# TubeBoard-Logic.net
KiCad netlist of a schematic drawn in EAGLE
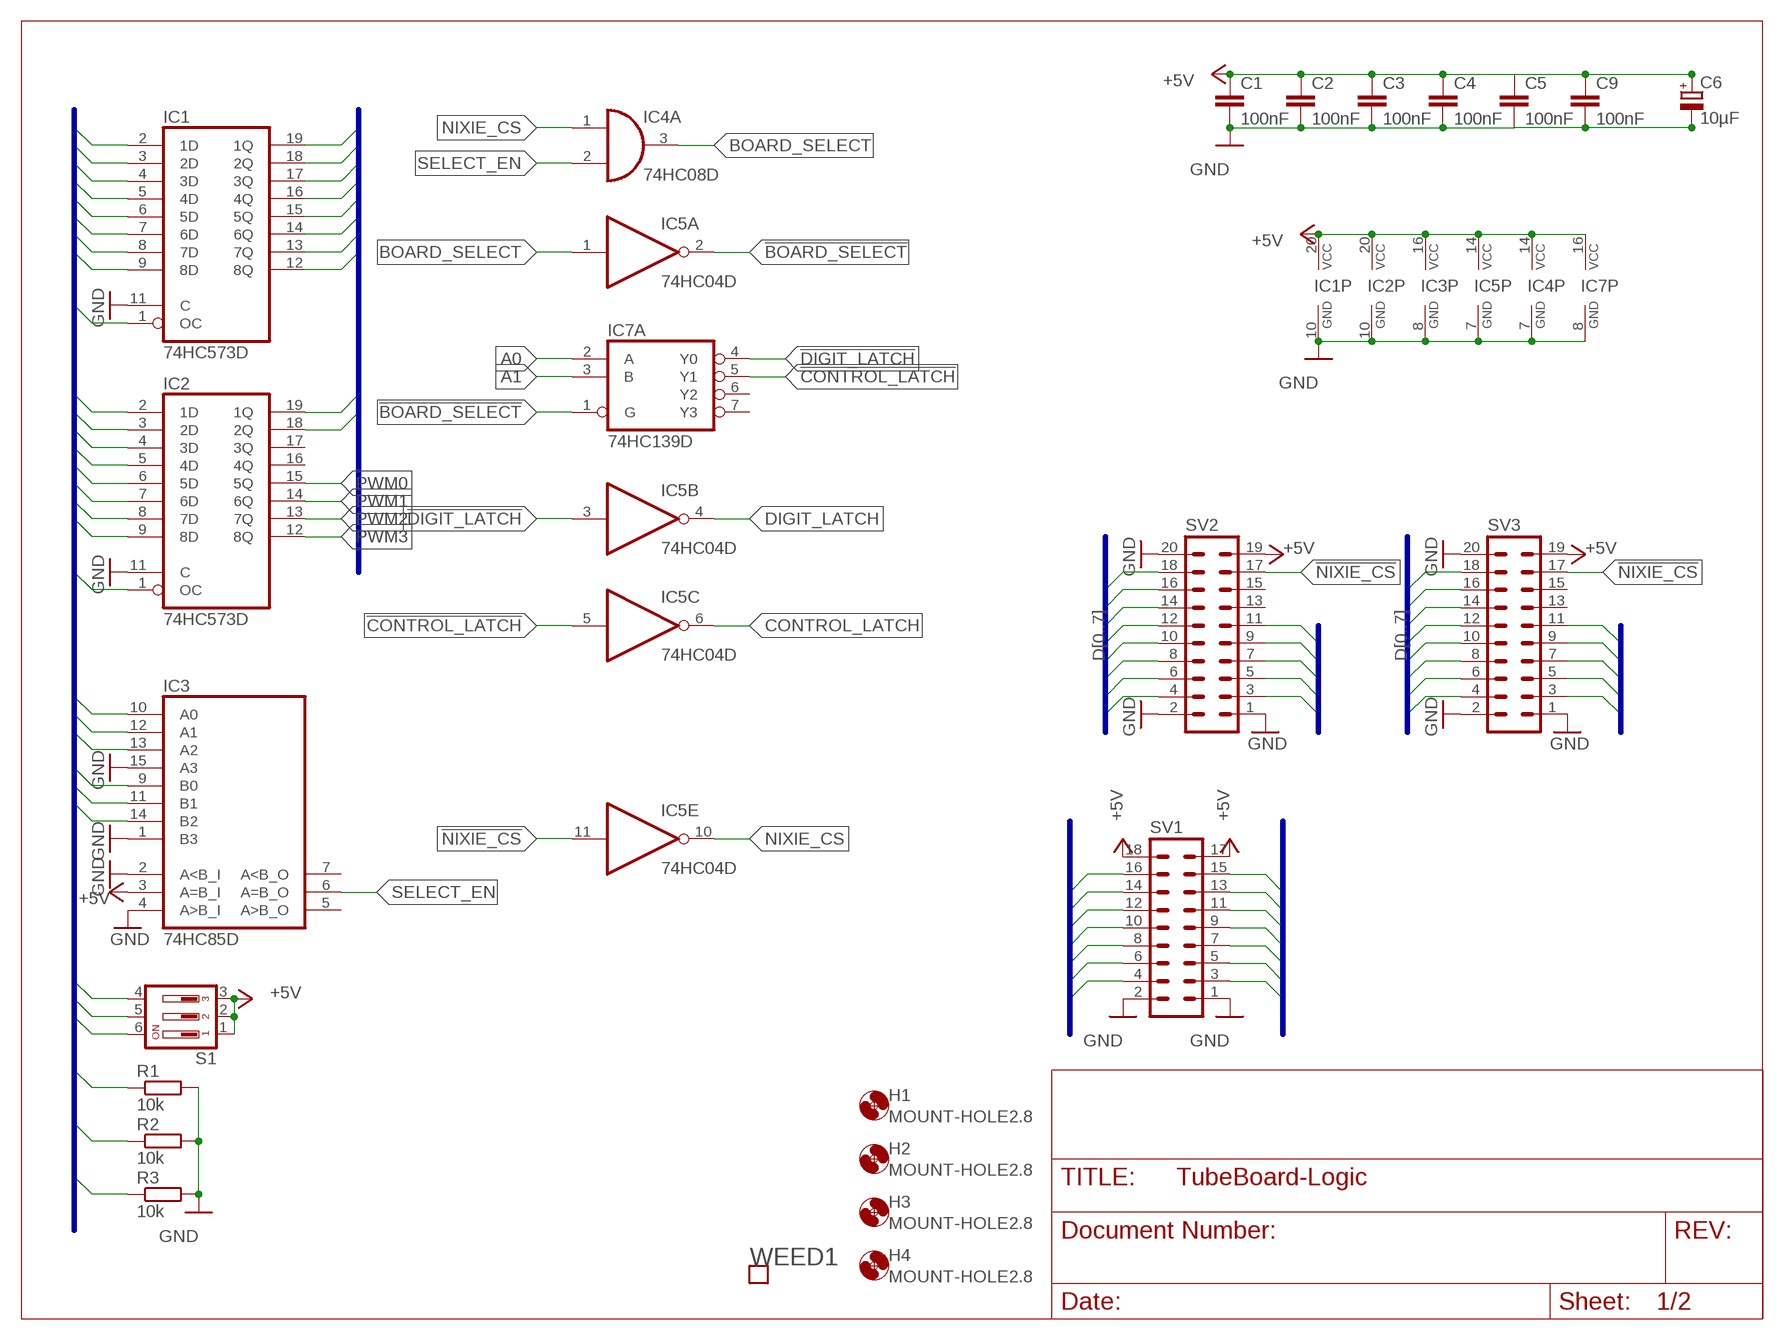
[diagram p0: schematic, sheet 1]
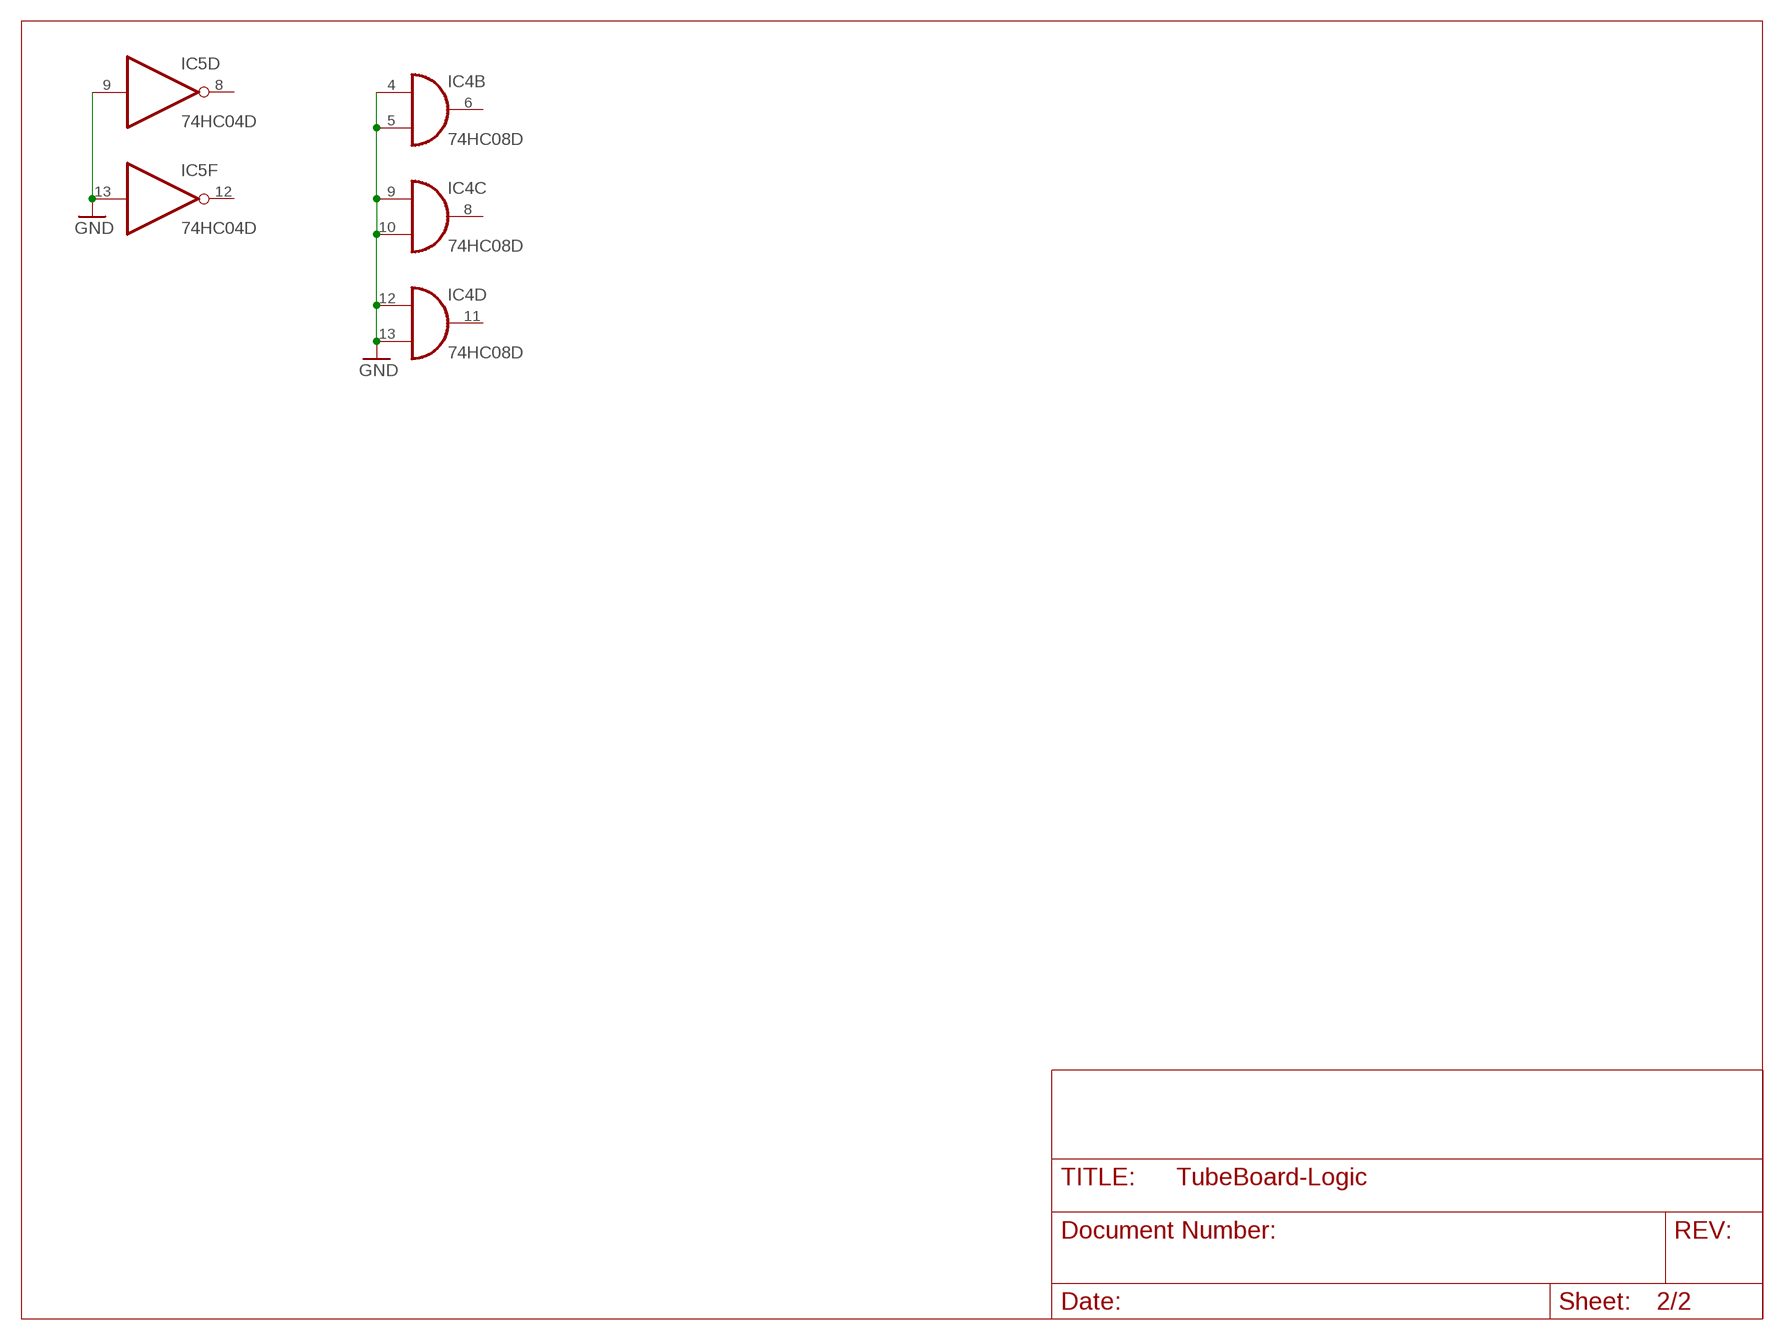
[diagram p1: schematic, sheet 2]

(export (version "E")
  (design (tool "Eeschema 10.0.6"))
  (components
    (comp (ref "C1")
      (value "100nF")
      (footprint "eagle-import:C1206")
      (libsource (lib "eagle-import") (part "C-EUC1206"))
    )
    (comp (ref "C2")
      (value "100nF")
      (footprint "eagle-import:C1206")
      (libsource (lib "eagle-import") (part "C-EUC1206"))
    )
    (comp (ref "C3")
      (value "100nF")
      (footprint "eagle-import:C1206")
      (libsource (lib "eagle-import") (part "C-EUC1206"))
    )
    (comp (ref "C4")
      (value "100nF")
      (footprint "eagle-import:C1206")
      (libsource (lib "eagle-import") (part "C-EUC1206"))
    )
    (comp (ref "C5")
      (value "100nF")
      (footprint "eagle-import:C1206")
      (libsource (lib "eagle-import") (part "C-EUC1206"))
    )
    (comp (ref "C6")
      (value "10µF")
      (footprint "eagle-import:SMC_B")
      (libsource (lib "eagle-import") (part "CPOL-EUSMCB"))
    )
    (comp (ref "C9")
      (value "100nF")
      (footprint "eagle-import:C1206")
      (libsource (lib "eagle-import") (part "C-EUC1206"))
    )
    (comp (ref "H1")
      (value "MOUNT-HOLE2.8")
      (footprint "eagle-import:2,8")
      (libsource (lib "eagle-import") (part "MOUNT-HOLE2.8"))
    )
    (comp (ref "H2")
      (value "MOUNT-HOLE2.8")
      (footprint "eagle-import:2,8")
      (libsource (lib "eagle-import") (part "MOUNT-HOLE2.8"))
    )
    (comp (ref "H3")
      (value "MOUNT-HOLE2.8")
      (footprint "eagle-import:2,8")
      (libsource (lib "eagle-import") (part "MOUNT-HOLE2.8"))
    )
    (comp (ref "H4")
      (value "MOUNT-HOLE2.8")
      (footprint "eagle-import:2,8")
      (libsource (lib "eagle-import") (part "MOUNT-HOLE2.8"))
    )
    (comp (ref "IC1")
      (value "74HC573D")
      (footprint "eagle-import:SO20W")
      (libsource (lib "eagle-import") (part "74573DHC"))
    )
    (comp (ref "IC2")
      (value "74HC573D")
      (footprint "eagle-import:SO20W")
      (libsource (lib "eagle-import") (part "74573DHC"))
    )
    (comp (ref "IC3")
      (value "74HC85D")
      (footprint "eagle-import:SO16")
      (fields (field (name "MOUSER") "771-74HC85D-T"))
      (libsource (lib "eagle-import") (part "7485DHC"))
    )
    (comp (ref "IC4")
      (value "74HC08D")
      (footprint "eagle-import:SO14")
      (libsource (lib "eagle-import") (part "7408DHC"))
    )
    (comp (ref "IC5")
      (value "74HC04D")
      (footprint "eagle-import:SO14")
      (libsource (lib "eagle-import") (part "7404DHC"))
    )
    (comp (ref "IC7")
      (value "74HC139D")
      (footprint "eagle-import:SO16")
      (fields (field (name "MOUSER") "771-HC139D652"))
      (libsource (lib "eagle-import") (part "74139DHC"))
    )
    (comp (ref "R1")
      (value "10k")
      (footprint "eagle-import:R2012")
      (libsource (lib "eagle-import") (part "R-EU_R2012"))
    )
    (comp (ref "R2")
      (value "10k")
      (footprint "eagle-import:R2012")
      (libsource (lib "eagle-import") (part "R-EU_R2012"))
    )
    (comp (ref "R3")
      (value "10k")
      (footprint "eagle-import:R2012")
      (libsource (lib "eagle-import") (part "R-EU_R2012"))
    )
    (comp (ref "S1")
      (value "SD4-03")
      (footprint "eagle-import:SD4-03")
      (libsource (lib "eagle-import") (part "SD4-03"))
    )
    (comp (ref "SV1")
      (value "MA09-2")
      (footprint "eagle-import:MA09-2")
      (libsource (lib "eagle-import") (part "MA09-2"))
    )
    (comp (ref "SV2")
      (value "MA10-2")
      (footprint "eagle-import:MA10-2")
      (libsource (lib "eagle-import") (part "MA10-2"))
    )
    (comp (ref "SV3")
      (value "MA10-2")
      (footprint "eagle-import:MA10-2")
      (libsource (lib "eagle-import") (part "MA10-2"))
    )
    (comp (ref "WEED1")
      (value "WEED")
      (footprint "eagle-import:DOINK")
      (libsource (lib "eagle-import") (part "WEED"))
    )
  )
  (nets
    (net (code "16") (name "+5V") (class "Default")
      (node (ref "C1") (pin "1") (pinfunction "1_1") (pintype "passive"))
      (node (ref "C2") (pin "1") (pinfunction "1_1") (pintype "passive"))
      (node (ref "C3") (pin "1") (pinfunction "1_1") (pintype "passive"))
      (node (ref "C4") (pin "1") (pinfunction "1_1") (pintype "passive"))
      (node (ref "C5") (pin "1") (pinfunction "1_1") (pintype "passive"))
      (node (ref "C6") (pin "+") (pinfunction "+_+") (pintype "passive"))
      (node (ref "C9") (pin "1") (pinfunction "1_1") (pintype "passive"))
      (node (ref "IC1") (pin "20") (pinfunction "VCC_20") (pintype "power_in"))
      (node (ref "IC2") (pin "20") (pinfunction "VCC_20") (pintype "power_in"))
      (node (ref "IC3") (pin "16") (pinfunction "VCC_16") (pintype "power_in"))
      (node (ref "IC3") (pin "3") (pinfunction "A=B_I_3") (pintype "input"))
      (node (ref "IC4") (pin "14") (pinfunction "VCC_14") (pintype "power_in"))
      (node (ref "IC5") (pin "14") (pinfunction "VCC_14") (pintype "power_in"))
      (node (ref "IC7") (pin "16") (pinfunction "VCC_16") (pintype "power_in"))
      (node (ref "S1") (pin "1") (pinfunction "1_1") (pintype "passive"))
      (node (ref "S1") (pin "2") (pinfunction "2_2") (pintype "passive"))
      (node (ref "S1") (pin "3") (pinfunction "3_3") (pintype "passive"))
      (node (ref "SV1") (pin "17") (pinfunction "17_17") (pintype "passive"))
      (node (ref "SV1") (pin "18") (pinfunction "18_18") (pintype "passive"))
      (node (ref "SV2") (pin "19") (pinfunction "19_19") (pintype "passive"))
      (node (ref "SV3") (pin "19") (pinfunction "19_19") (pintype "passive"))
    )
    (net (code "20") (name "A0") (class "Default")
      (node (ref "IC7") (pin "2") (pinfunction "A_2") (pintype "input"))
      (node (ref "SV2") (pin "3") (pinfunction "3_3") (pintype "passive"))
      (node (ref "SV3") (pin "3") (pinfunction "3_3") (pintype "passive"))
    )
    (net (code "21") (name "A1") (class "Default")
      (node (ref "IC7") (pin "3") (pinfunction "B_3") (pintype "input"))
      (node (ref "SV2") (pin "5") (pinfunction "5_5") (pintype "passive"))
      (node (ref "SV3") (pin "5") (pinfunction "5_5") (pintype "passive"))
    )
    (net (code "22") (name "A2") (class "Default")
      (node (ref "IC3") (pin "10") (pinfunction "A0_10") (pintype "input"))
      (node (ref "SV2") (pin "7") (pinfunction "7_7") (pintype "passive"))
      (node (ref "SV3") (pin "7") (pinfunction "7_7") (pintype "passive"))
    )
    (net (code "23") (name "A3") (class "Default")
      (node (ref "IC3") (pin "12") (pinfunction "A1_12") (pintype "input"))
      (node (ref "SV2") (pin "9") (pinfunction "9_9") (pintype "passive"))
      (node (ref "SV3") (pin "9") (pinfunction "9_9") (pintype "passive"))
    )
    (net (code "24") (name "A4") (class "Default")
      (node (ref "IC3") (pin "13") (pinfunction "A2_13") (pintype "input"))
      (node (ref "SV2") (pin "11") (pinfunction "11_11") (pintype "passive"))
      (node (ref "SV3") (pin "11") (pinfunction "11_11") (pintype "passive"))
    )
    (net (code "25") (name "BOARD_SELECT") (class "Default")
      (node (ref "IC4") (pin "3") (pinfunction "O_3") (pintype "output"))
      (node (ref "IC5") (pin "1") (pinfunction "I_1") (pintype "input"))
    )
    (net (code "26") (name "COLON_B") (class "Default")
      (node (ref "IC2") (pin "19") (pinfunction "1Q_19") (pintype "tri_state"))
      (node (ref "SV1") (pin "8") (pinfunction "8_8") (pintype "passive"))
    )
    (net (code "27") (name "COLON_T") (class "Default")
      (node (ref "IC2") (pin "18") (pinfunction "2Q_18") (pintype "tri_state"))
      (node (ref "SV1") (pin "6") (pinfunction "6_6") (pintype "passive"))
    )
    (net (code "28") (name "CONTROL_LATCH") (class "Default")
      (node (ref "IC2") (pin "1") (pinfunction "OC_1") (pintype "input"))
      (node (ref "IC5") (pin "6") (pinfunction "O_6") (pintype "output"))
    )
    (net (code "29") (name "D0") (class "Default")
      (node (ref "IC1") (pin "2") (pinfunction "1D_2") (pintype "input"))
      (node (ref "IC2") (pin "2") (pinfunction "1D_2") (pintype "input"))
      (node (ref "SV2") (pin "8") (pinfunction "8_8") (pintype "passive"))
      (node (ref "SV3") (pin "8") (pinfunction "8_8") (pintype "passive"))
    )
    (net (code "30") (name "D1") (class "Default")
      (node (ref "IC1") (pin "3") (pinfunction "2D_3") (pintype "input"))
      (node (ref "IC2") (pin "3") (pinfunction "2D_3") (pintype "input"))
      (node (ref "SV2") (pin "6") (pinfunction "6_6") (pintype "passive"))
      (node (ref "SV3") (pin "6") (pinfunction "6_6") (pintype "passive"))
    )
    (net (code "31") (name "D2") (class "Default")
      (node (ref "IC1") (pin "4") (pinfunction "3D_4") (pintype "input"))
      (node (ref "IC2") (pin "4") (pinfunction "3D_4") (pintype "input"))
      (node (ref "SV2") (pin "4") (pinfunction "4_4") (pintype "passive"))
      (node (ref "SV3") (pin "4") (pinfunction "4_4") (pintype "passive"))
    )
    (net (code "32") (name "D3") (class "Default")
      (node (ref "IC1") (pin "5") (pinfunction "4D_5") (pintype "input"))
      (node (ref "IC2") (pin "5") (pinfunction "4D_5") (pintype "input"))
      (node (ref "SV2") (pin "10") (pinfunction "10_10") (pintype "passive"))
      (node (ref "SV3") (pin "10") (pinfunction "10_10") (pintype "passive"))
    )
    (net (code "33") (name "D4") (class "Default")
      (node (ref "IC1") (pin "6") (pinfunction "5D_6") (pintype "input"))
      (node (ref "IC2") (pin "6") (pinfunction "5D_6") (pintype "input"))
      (node (ref "SV2") (pin "12") (pinfunction "12_12") (pintype "passive"))
      (node (ref "SV3") (pin "12") (pinfunction "12_12") (pintype "passive"))
    )
    (net (code "34") (name "D5") (class "Default")
      (node (ref "IC1") (pin "7") (pinfunction "6D_7") (pintype "input"))
      (node (ref "IC2") (pin "7") (pinfunction "6D_7") (pintype "input"))
      (node (ref "SV2") (pin "14") (pinfunction "14_14") (pintype "passive"))
      (node (ref "SV3") (pin "14") (pinfunction "14_14") (pintype "passive"))
    )
    (net (code "35") (name "D6") (class "Default")
      (node (ref "IC1") (pin "8") (pinfunction "7D_8") (pintype "input"))
      (node (ref "IC2") (pin "8") (pinfunction "7D_8") (pintype "input"))
      (node (ref "SV2") (pin "16") (pinfunction "16_16") (pintype "passive"))
      (node (ref "SV3") (pin "16") (pinfunction "16_16") (pintype "passive"))
    )
    (net (code "36") (name "D7") (class "Default")
      (node (ref "IC1") (pin "9") (pinfunction "8D_9") (pintype "input"))
      (node (ref "IC2") (pin "9") (pinfunction "8D_9") (pintype "input"))
      (node (ref "SV2") (pin "18") (pinfunction "18_18") (pintype "passive"))
      (node (ref "SV3") (pin "18") (pinfunction "18_18") (pintype "passive"))
    )
    (net (code "37") (name "DIGIT_LATCH") (class "Default")
      (node (ref "IC1") (pin "1") (pinfunction "OC_1") (pintype "input"))
      (node (ref "IC5") (pin "4") (pinfunction "O_4") (pintype "output"))
    )
    (net (code "38") (name "GND") (class "Default")
      (node (ref "C1") (pin "2") (pinfunction "2_2") (pintype "passive"))
      (node (ref "C2") (pin "2") (pinfunction "2_2") (pintype "passive"))
      (node (ref "C3") (pin "2") (pinfunction "2_2") (pintype "passive"))
      (node (ref "C4") (pin "2") (pinfunction "2_2") (pintype "passive"))
      (node (ref "C5") (pin "2") (pinfunction "2_2") (pintype "passive"))
      (node (ref "C6") (pin "-") (pinfunction "-_-") (pintype "passive"))
      (node (ref "C9") (pin "2") (pinfunction "2_2") (pintype "passive"))
      (node (ref "IC1") (pin "10") (pinfunction "GND_10") (pintype "power_in"))
      (node (ref "IC1") (pin "11") (pinfunction "C_11") (pintype "input"))
      (node (ref "IC2") (pin "10") (pinfunction "GND_10") (pintype "power_in"))
      (node (ref "IC2") (pin "11") (pinfunction "C_11") (pintype "input"))
      (node (ref "IC3") (pin "1") (pinfunction "B3_1") (pintype "input"))
      (node (ref "IC3") (pin "15") (pinfunction "A3_15") (pintype "input"))
      (node (ref "IC3") (pin "2") (pinfunction "A<B_I_2") (pintype "input"))
      (node (ref "IC3") (pin "4") (pinfunction "A>B_I_4") (pintype "input"))
      (node (ref "IC3") (pin "8") (pinfunction "GND_8") (pintype "power_in"))
      (node (ref "IC4") (pin "10") (pinfunction "I1_10") (pintype "input"))
      (node (ref "IC4") (pin "12") (pinfunction "I0_12") (pintype "input"))
      (node (ref "IC4") (pin "13") (pinfunction "I1_13") (pintype "input"))
      (node (ref "IC4") (pin "4") (pinfunction "I0_4") (pintype "input"))
      (node (ref "IC4") (pin "5") (pinfunction "I1_5") (pintype "input"))
      (node (ref "IC4") (pin "7") (pinfunction "GND_7") (pintype "power_in"))
      (node (ref "IC4") (pin "9") (pinfunction "I0_9") (pintype "input"))
      (node (ref "IC5") (pin "13") (pinfunction "I_13") (pintype "input"))
      (node (ref "IC5") (pin "7") (pinfunction "GND_7") (pintype "power_in"))
      (node (ref "IC5") (pin "9") (pinfunction "I_9") (pintype "input"))
      (node (ref "IC7") (pin "8") (pinfunction "GND_8") (pintype "power_in"))
      (node (ref "R1") (pin "2") (pinfunction "2_2") (pintype "passive"))
      (node (ref "R2") (pin "2") (pinfunction "2_2") (pintype "passive"))
      (node (ref "R3") (pin "2") (pinfunction "2_2") (pintype "passive"))
      (node (ref "SV1") (pin "1") (pinfunction "1_1") (pintype "passive"))
      (node (ref "SV1") (pin "2") (pinfunction "2_2") (pintype "passive"))
      (node (ref "SV2") (pin "1") (pinfunction "1_1") (pintype "passive"))
      (node (ref "SV2") (pin "2") (pinfunction "2_2") (pintype "passive"))
      (node (ref "SV2") (pin "20") (pinfunction "20_20") (pintype "passive"))
      (node (ref "SV3") (pin "1") (pinfunction "1_1") (pintype "passive"))
      (node (ref "SV3") (pin "2") (pinfunction "2_2") (pintype "passive"))
      (node (ref "SV3") (pin "20") (pinfunction "20_20") (pintype "passive"))
    )
    (net (code "39") (name "ID0") (class "Default")
      (node (ref "IC3") (pin "9") (pinfunction "B0_9") (pintype "input"))
      (node (ref "R3") (pin "1") (pinfunction "1_1") (pintype "passive"))
      (node (ref "S1") (pin "6") (pinfunction "6_6") (pintype "passive"))
    )
    (net (code "40") (name "ID1") (class "Default")
      (node (ref "IC3") (pin "11") (pinfunction "B1_11") (pintype "input"))
      (node (ref "R2") (pin "1") (pinfunction "1_1") (pintype "passive"))
      (node (ref "S1") (pin "5") (pinfunction "5_5") (pintype "passive"))
    )
    (net (code "41") (name "ID2") (class "Default")
      (node (ref "IC3") (pin "14") (pinfunction "B2_14") (pintype "input"))
      (node (ref "R1") (pin "1") (pinfunction "1_1") (pintype "passive"))
      (node (ref "S1") (pin "4") (pinfunction "4_4") (pintype "passive"))
    )
    (net (code "42") (name "LDIGIT0") (class "Default")
      (node (ref "IC1") (pin "19") (pinfunction "1Q_19") (pintype "tri_state"))
      (node (ref "SV1") (pin "16") (pinfunction "16_16") (pintype "passive"))
    )
    (net (code "43") (name "LDIGIT1") (class "Default")
      (node (ref "IC1") (pin "18") (pinfunction "2Q_18") (pintype "tri_state"))
      (node (ref "SV1") (pin "14") (pinfunction "14_14") (pintype "passive"))
    )
    (net (code "44") (name "LDIGIT2") (class "Default")
      (node (ref "IC1") (pin "17") (pinfunction "3Q_17") (pintype "tri_state"))
      (node (ref "SV1") (pin "12") (pinfunction "12_12") (pintype "passive"))
    )
    (net (code "45") (name "LDIGIT3") (class "Default")
      (node (ref "IC1") (pin "16") (pinfunction "4Q_16") (pintype "tri_state"))
      (node (ref "SV1") (pin "10") (pinfunction "10_10") (pintype "passive"))
    )
    (net (code "46") (name "NIXIE_CS") (class "Default")
      (node (ref "IC4") (pin "1") (pinfunction "I0_1") (pintype "input"))
      (node (ref "IC5") (pin "10") (pinfunction "O_10") (pintype "output"))
    )
    (net (code "47") (name "PWM0") (class "Default")
      (node (ref "IC2") (pin "15") (pinfunction "5Q_15") (pintype "tri_state"))
      (node (ref "SV1") (pin "7") (pinfunction "7_7") (pintype "passive"))
    )
    (net (code "48") (name "PWM1") (class "Default")
      (node (ref "IC2") (pin "14") (pinfunction "6Q_14") (pintype "tri_state"))
      (node (ref "SV1") (pin "5") (pinfunction "5_5") (pintype "passive"))
    )
    (net (code "49") (name "PWM2") (class "Default")
      (node (ref "IC2") (pin "13") (pinfunction "7Q_13") (pintype "tri_state"))
      (node (ref "SV1") (pin "3") (pinfunction "3_3") (pintype "passive"))
    )
    (net (code "50") (name "PWM3") (class "Default")
      (node (ref "IC2") (pin "12") (pinfunction "8Q_12") (pintype "tri_state"))
      (node (ref "SV1") (pin "4") (pinfunction "4_4") (pintype "passive"))
    )
    (net (code "51") (name "RDIGIT0") (class "Default")
      (node (ref "IC1") (pin "15") (pinfunction "5Q_15") (pintype "tri_state"))
      (node (ref "SV1") (pin "15") (pinfunction "15_15") (pintype "passive"))
    )
    (net (code "52") (name "RDIGIT1") (class "Default")
      (node (ref "IC1") (pin "14") (pinfunction "6Q_14") (pintype "tri_state"))
      (node (ref "SV1") (pin "13") (pinfunction "13_13") (pintype "passive"))
    )
    (net (code "53") (name "RDIGIT2") (class "Default")
      (node (ref "IC1") (pin "13") (pinfunction "7Q_13") (pintype "tri_state"))
      (node (ref "SV1") (pin "11") (pinfunction "11_11") (pintype "passive"))
    )
    (net (code "54") (name "RDIGIT3") (class "Default")
      (node (ref "IC1") (pin "12") (pinfunction "8Q_12") (pintype "tri_state"))
      (node (ref "SV1") (pin "9") (pinfunction "9_9") (pintype "passive"))
    )
    (net (code "55") (name "SELECT_EN") (class "Default")
      (node (ref "IC3") (pin "6") (pinfunction "A=B_O_6") (pintype "output"))
      (node (ref "IC4") (pin "2") (pinfunction "I1_2") (pintype "input"))
    )
    (net (code "56") (name "unconnected-(IC2A-3Q-Pad17)") (class "Default")
      (node (ref "IC2") (pin "17") (pinfunction "3Q_17") (pintype "tri_state"))
    )
    (net (code "57") (name "unconnected-(IC2A-4Q-Pad16)") (class "Default")
      (node (ref "IC2") (pin "16") (pinfunction "4Q_16") (pintype "tri_state"))
    )
    (net (code "58") (name "unconnected-(IC3A-A<B_O-Pad7)") (class "Default")
      (node (ref "IC3") (pin "7") (pinfunction "A<B_O_7") (pintype "output"))
    )
    (net (code "59") (name "unconnected-(IC3A-A>B_O-Pad5)") (class "Default")
      (node (ref "IC3") (pin "5") (pinfunction "A>B_O_5") (pintype "output"))
    )
    (net (code "60") (name "unconnected-(IC4B-O-Pad6)") (class "Default")
      (node (ref "IC4") (pin "6") (pinfunction "O_6") (pintype "output"))
    )
    (net (code "61") (name "unconnected-(IC4C-O-Pad8)") (class "Default")
      (node (ref "IC4") (pin "8") (pinfunction "O_8") (pintype "output"))
    )
    (net (code "62") (name "unconnected-(IC4D-O-Pad11)") (class "Default")
      (node (ref "IC4") (pin "11") (pinfunction "O_11") (pintype "output"))
    )
    (net (code "63") (name "unconnected-(IC5D-O-Pad8)") (class "Default")
      (node (ref "IC5") (pin "8") (pinfunction "O_8") (pintype "output"))
    )
    (net (code "64") (name "unconnected-(IC5F-O-Pad12)") (class "Default")
      (node (ref "IC5") (pin "12") (pinfunction "O_12") (pintype "output"))
    )
    (net (code "65") (name "unconnected-(IC7A-Y2-Pad6)") (class "Default")
      (node (ref "IC7") (pin "6") (pinfunction "Y2_6") (pintype "output"))
    )
    (net (code "66") (name "unconnected-(IC7A-Y3-Pad7)") (class "Default")
      (node (ref "IC7") (pin "7") (pinfunction "Y3_7") (pintype "output"))
    )
    (net (code "67") (name "unconnected-(SV2-Pad13)") (class "Default")
      (node (ref "SV2") (pin "13") (pinfunction "13_13") (pintype "passive"))
    )
    (net (code "68") (name "unconnected-(SV2-Pad15)") (class "Default")
      (node (ref "SV2") (pin "15") (pinfunction "15_15") (pintype "passive"))
    )
    (net (code "69") (name "unconnected-(SV3-Pad13)") (class "Default")
      (node (ref "SV3") (pin "13") (pinfunction "13_13") (pintype "passive"))
    )
    (net (code "70") (name "unconnected-(SV3-Pad15)") (class "Default")
      (node (ref "SV3") (pin "15") (pinfunction "15_15") (pintype "passive"))
    )
    (net (code "71") (name "~{BOARD_SELECT}") (class "Default")
      (node (ref "IC5") (pin "2") (pinfunction "O_2") (pintype "output"))
      (node (ref "IC7") (pin "1") (pinfunction "G_1") (pintype "input"))
    )
    (net (code "72") (name "~{CONTROL_LATCH}") (class "Default")
      (node (ref "IC5") (pin "5") (pinfunction "I_5") (pintype "input"))
      (node (ref "IC7") (pin "5") (pinfunction "Y1_5") (pintype "output"))
    )
    (net (code "73") (name "~{DIGIT_LATCH}") (class "Default")
      (node (ref "IC5") (pin "3") (pinfunction "I_3") (pintype "input"))
      (node (ref "IC7") (pin "4") (pinfunction "Y0_4") (pintype "output"))
    )
    (net (code "74") (name "~{NIXIE_CS}") (class "Default")
      (node (ref "IC5") (pin "11") (pinfunction "I_11") (pintype "input"))
      (node (ref "SV2") (pin "17") (pinfunction "17_17") (pintype "passive"))
      (node (ref "SV3") (pin "17") (pinfunction "17_17") (pintype "passive"))
    )
  )
)
